# scout_mk1_b.net
KiCad netlist of a schematic drawn in EAGLE
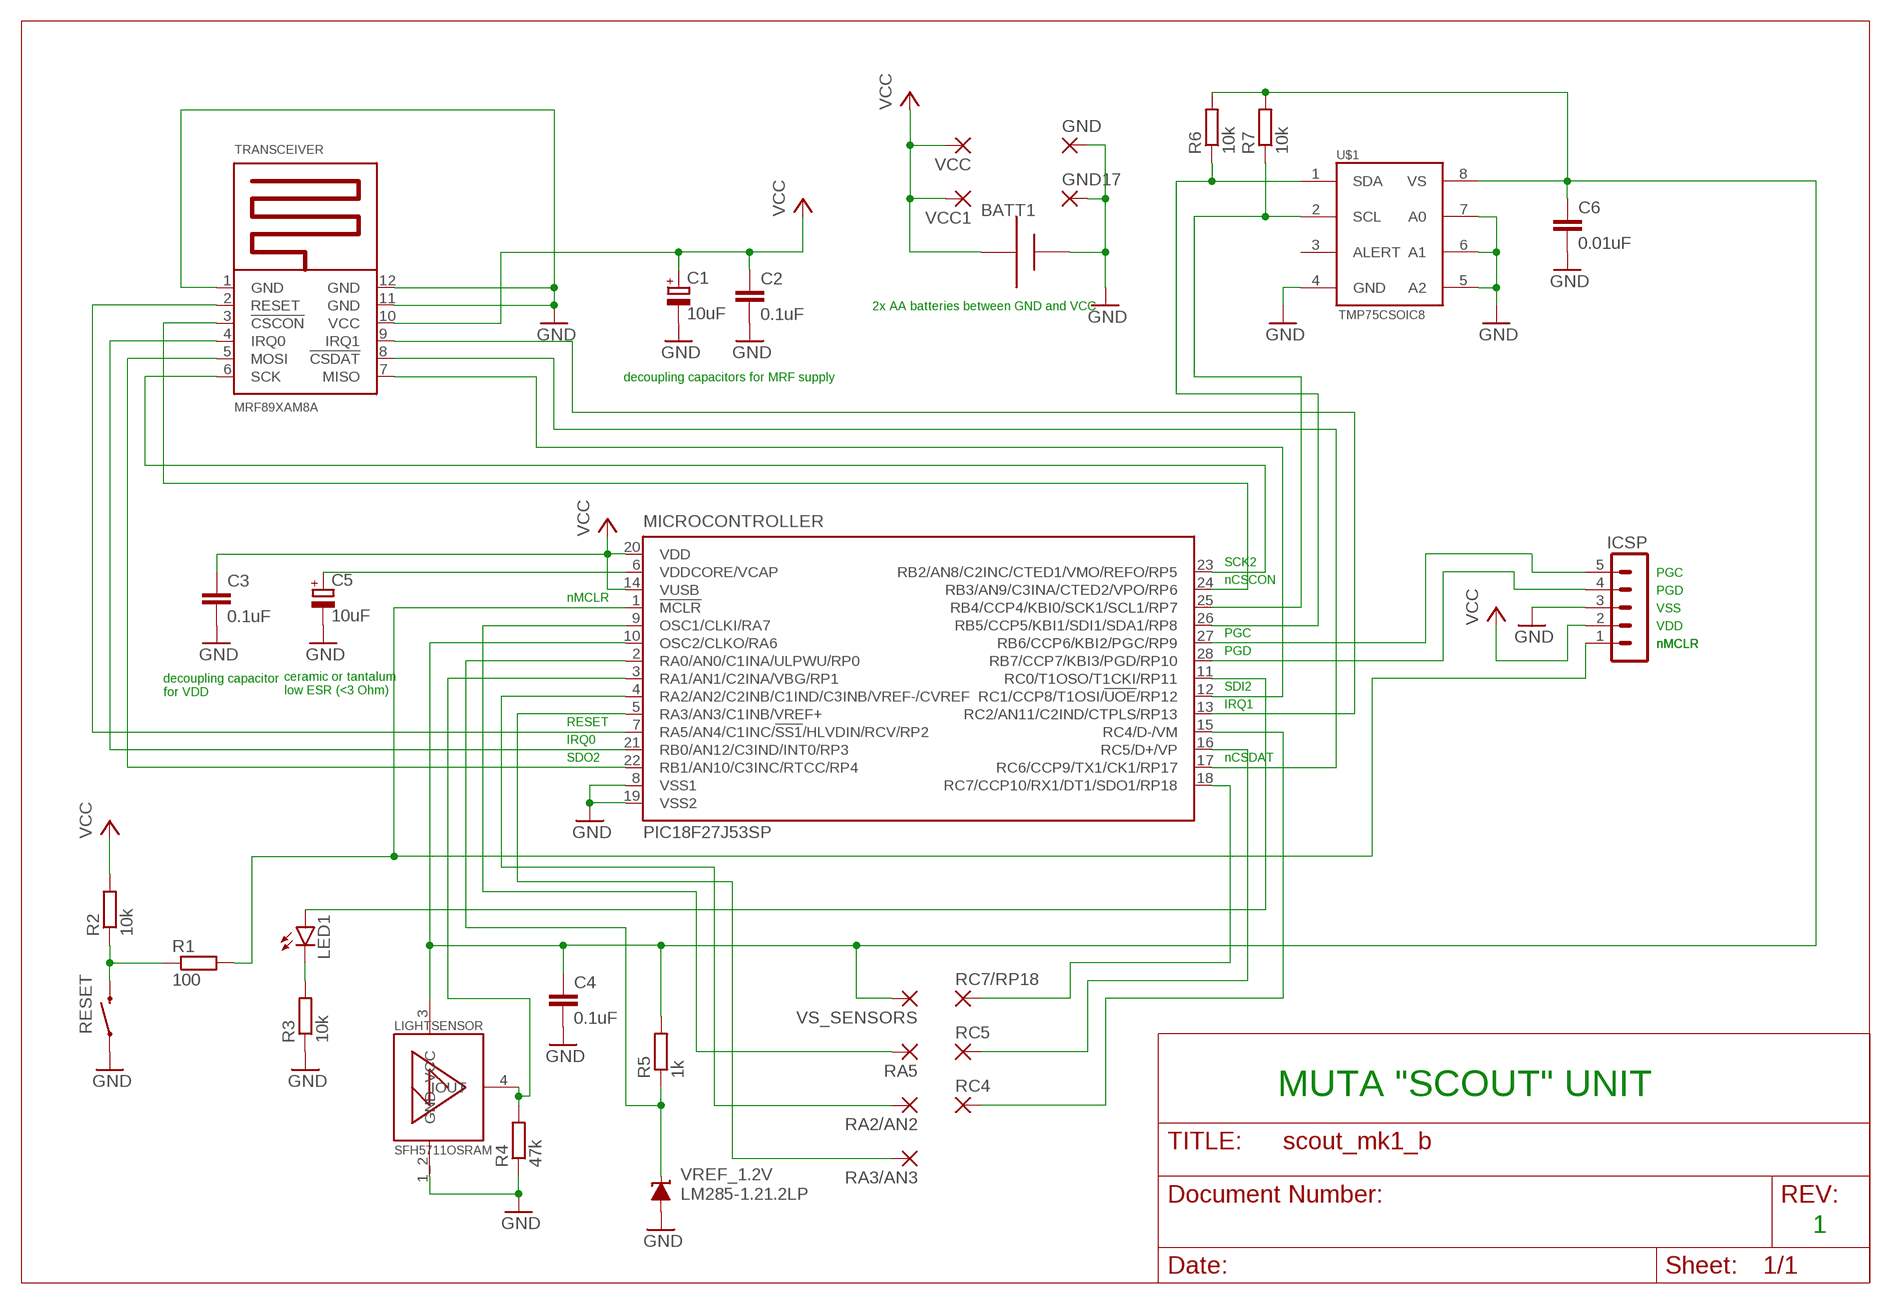
[diagram p0: schematic, sheet 1]

(export (version "E")
  (design (tool "Eeschema 10.0.6"))
  (components
    (comp (ref "BATT1")
      (value "AAA")
      (footprint "eagle-import:2XAAA")
      (libsource (lib "eagle-import") (part "AAA"))
    )
    (comp (ref "C1")
      (value "10uF")
      (footprint "eagle-import:TT5D6")
      (libsource (lib "eagle-import") (part "CPOL-EUTT6D6"))
    )
    (comp (ref "C2")
      (value "0.1uF")
      (footprint "eagle-import:C050-025X075")
      (libsource (lib "eagle-import") (part "C-EU050-025X075"))
    )
    (comp (ref "C3")
      (value "0.1uF")
      (footprint "eagle-import:C050-025X075")
      (libsource (lib "eagle-import") (part "C-EU050-025X075"))
    )
    (comp (ref "C4")
      (value "0.1uF")
      (footprint "eagle-import:C050-025X075")
      (libsource (lib "eagle-import") (part "C-EU050-025X075"))
    )
    (comp (ref "C5")
      (value "10uF")
      (footprint "eagle-import:C_6032-28R")
      (libsource (lib "eagle-import") (part "CPOL-EUC/6032-28R"))
    )
    (comp (ref "C6")
      (value "0.01uF")
      (footprint "eagle-import:C050-025X075")
      (libsource (lib "eagle-import") (part "C-EU050-025X075"))
    )
    (comp (ref "GND")
      (value "3,81/1,1")
      (footprint "eagle-import:3,81_1,1")
      (libsource (lib "eagle-import") (part "3,81/1,1"))
    )
    (comp (ref "GND17")
      (value "3,81/1,1")
      (footprint "eagle-import:3,81_1,1")
      (libsource (lib "eagle-import") (part "3,81/1,1"))
    )
    (comp (ref "ICSP")
      (value "MA05-1")
      (footprint "eagle-import:MA05-1")
      (libsource (lib "eagle-import") (part "MA05-1"))
    )
    (comp (ref "LED1")
      (value "LED1206")
      (footprint "eagle-import:LED-1206")
      (libsource (lib "eagle-import") (part "LED1206"))
    )
    (comp (ref "LIGHTSENSOR")
      (value "SFH5711OSRAM")
      (footprint "eagle-import:SFH5711")
      (libsource (lib "eagle-import") (part "SFH5711OSRAM"))
    )
    (comp (ref "MICROCONTROLLER")
      (value "PIC18F27J53SP")
      (footprint "eagle-import:DIL28-3")
      (fields (field (name "MPN") "PIC18F27J53-I/SP"))
      (libsource (lib "eagle-import") (part "PIC18F2J53SP7"))
    )
    (comp (ref "R1")
      (value "100")
      (footprint "eagle-import:0207_10")
      (libsource (lib "eagle-import") (part "R-EU_0207_10"))
    )
    (comp (ref "R2")
      (value "10k")
      (footprint "eagle-import:0207_10")
      (libsource (lib "eagle-import") (part "R-EU_0207_10"))
    )
    (comp (ref "R3")
      (value "10k")
      (footprint "eagle-import:0207_2V")
      (libsource (lib "eagle-import") (part "R-EU_0207_2V"))
    )
    (comp (ref "R4")
      (value "47k")
      (footprint "eagle-import:0207_10")
      (libsource (lib "eagle-import") (part "R-EU_0207_10"))
    )
    (comp (ref "R5")
      (value "1k")
      (footprint "eagle-import:0207_10")
      (libsource (lib "eagle-import") (part "R-EU_0207_10"))
    )
    (comp (ref "R6")
      (value "10k")
      (footprint "eagle-import:0207_10")
      (libsource (lib "eagle-import") (part "R-EU_0207_10"))
    )
    (comp (ref "R7")
      (value "10k")
      (footprint "eagle-import:0207_10")
      (libsource (lib "eagle-import") (part "R-EU_0207_10"))
    )
    (comp (ref "RA2/AN2")
      (value "3,81/1,1")
      (footprint "eagle-import:3,81_1,1")
      (libsource (lib "eagle-import") (part "3,81/1,1"))
    )
    (comp (ref "RA3/AN3")
      (value "3,81/1,1")
      (footprint "eagle-import:3,81_1,1")
      (libsource (lib "eagle-import") (part "3,81/1,1"))
    )
    (comp (ref "RA5")
      (value "3,81/1,1")
      (footprint "eagle-import:3,81_1,1")
      (libsource (lib "eagle-import") (part "3,81/1,1"))
    )
    (comp (ref "RC4")
      (value "3,81/1,1")
      (footprint "eagle-import:3,81_1,1")
      (libsource (lib "eagle-import") (part "3,81/1,1"))
    )
    (comp (ref "RC5")
      (value "3,81/1,1")
      (footprint "eagle-import:3,81_1,1")
      (libsource (lib "eagle-import") (part "3,81/1,1"))
    )
    (comp (ref "RC7/RP18")
      (value "3,81/1,1")
      (footprint "eagle-import:3,81_1,1")
      (libsource (lib "eagle-import") (part "3,81/1,1"))
    )
    (comp (ref "RESET")
      (value "SWITCH-MOMENTARY-2PTH")
      (footprint "eagle-import:TACTILE-PTH")
      (libsource (lib "eagle-import") (part "SWITCH-MOMENTARY-2PTH"))
    )
    (comp (ref "TRANSCEIVER")
      (value "MRF89XAM8A")
      (footprint "eagle-import:MRF89XAMXA")
      (libsource (lib "eagle-import") (part "MRF89XAM8A"))
    )
    (comp (ref "U$1")
      (value "TMP75CSOIC8")
      (footprint "eagle-import:SOIC8")
      (libsource (lib "eagle-import") (part "TMP75CSOIC8"))
    )
    (comp (ref "VCC")
      (value "3,81/1,1")
      (footprint "eagle-import:3,81_1,1")
      (libsource (lib "eagle-import") (part "3,81/1,1"))
    )
    (comp (ref "VCC1")
      (value "3,81/1,1")
      (footprint "eagle-import:3,81_1,1")
      (libsource (lib "eagle-import") (part "3,81/1,1"))
    )
    (comp (ref "VREF_1.2V")
      (value "LM285-1.21.2LP")
      (footprint "eagle-import:LP_O-PBCY-W3")
      (libsource (lib "eagle-import") (part "LM285-1.21.2LP"))
    )
    (comp (ref "VS_SENSORS")
      (value "3,81/1,1")
      (footprint "eagle-import:3,81_1,1")
      (libsource (lib "eagle-import") (part "3,81/1,1"))
    )
  )
  (nets
    (net (code "1") (name "GND") (class "Default")
      (node (ref "BATT1") (pin "P$1") (pinfunction "+_P$1") (pintype "bidirectional"))
      (node (ref "C1") (pin "-") (pinfunction "-_-") (pintype "passive"))
      (node (ref "C2") (pin "2") (pinfunction "2_2") (pintype "passive"))
      (node (ref "C3") (pin "2") (pinfunction "2_2") (pintype "passive"))
      (node (ref "C4") (pin "2") (pinfunction "2_2") (pintype "passive"))
      (node (ref "C5") (pin "-") (pinfunction "-_-") (pintype "passive"))
      (node (ref "C6") (pin "2") (pinfunction "2_2") (pintype "passive"))
      (node (ref "GND") (pin "1") (pinfunction "P_1") (pintype "passive"))
      (node (ref "GND17") (pin "1") (pinfunction "P_1") (pintype "passive"))
      (node (ref "ICSP") (pin "3") (pinfunction "3_3") (pintype "passive"))
      (node (ref "LIGHTSENSOR") (pin "1_2") (pinfunction "GND_1_2") (pintype "bidirectional"))
      (node (ref "MICROCONTROLLER") (pin "19") (pinfunction "VSS2_19") (pintype "input"))
      (node (ref "MICROCONTROLLER") (pin "8") (pinfunction "VSS1_8") (pintype "input"))
      (node (ref "R3") (pin "1") (pinfunction "1_1") (pintype "passive"))
      (node (ref "R4") (pin "1") (pinfunction "1_1") (pintype "passive"))
      (node (ref "RESET") (pin "1") (pinfunction "1_1") (pintype "passive"))
      (node (ref "TRANSCEIVER") (pin "1") (pinfunction "GND_1") (pintype "power_in"))
      (node (ref "TRANSCEIVER") (pin "11") (pinfunction "GND_11") (pintype "power_in"))
      (node (ref "TRANSCEIVER") (pin "12") (pinfunction "GND_12") (pintype "power_in"))
      (node (ref "U$1") (pin "4") (pinfunction "GND_4") (pintype "bidirectional"))
      (node (ref "U$1") (pin "5") (pinfunction "A2_5") (pintype "bidirectional"))
      (node (ref "U$1") (pin "6") (pinfunction "A1_6") (pintype "bidirectional"))
      (node (ref "U$1") (pin "7") (pinfunction "A0_7") (pintype "bidirectional"))
      (node (ref "VREF_1.2V") (pin "3") (pinfunction "A_3") (pintype "passive"))
    )
    (net (code "2") (name "Net-(LED1-PadC)") (class "Default")
      (node (ref "LED1") (pin "C") (pinfunction "C_C") (pintype "passive"))
      (node (ref "R3") (pin "2") (pinfunction "2_2") (pintype "passive"))
    )
    (net (code "3") (name "Net-(LIGHTSENSOR-IOUT)") (class "Default")
      (node (ref "LIGHTSENSOR") (pin "4") (pinfunction "IOUT_4") (pintype "bidirectional"))
      (node (ref "MICROCONTROLLER") (pin "3") (pinfunction "RA1/AN1/C2INA/VBG/RP1_3") (pintype "bidirectional"))
      (node (ref "R4") (pin "2") (pinfunction "2_2") (pintype "passive"))
    )
    (net (code "4") (name "Net-(LIGHTSENSOR-VCC)") (class "Default")
      (node (ref "C4") (pin "1") (pinfunction "1_1") (pintype "passive"))
      (node (ref "C6") (pin "1") (pinfunction "1_1") (pintype "passive"))
      (node (ref "LIGHTSENSOR") (pin "3") (pinfunction "VCC_3") (pintype "bidirectional"))
      (node (ref "MICROCONTROLLER") (pin "10") (pinfunction "OSC2/CLKO/RA6_10") (pintype "bidirectional"))
      (node (ref "R5") (pin "2") (pinfunction "2_2") (pintype "passive"))
      (node (ref "R6") (pin "2") (pinfunction "2_2") (pintype "passive"))
      (node (ref "R7") (pin "2") (pinfunction "2_2") (pintype "passive"))
      (node (ref "U$1") (pin "8") (pinfunction "VS_8") (pintype "bidirectional"))
      (node (ref "VS_SENSORS") (pin "1") (pinfunction "P_1") (pintype "passive"))
    )
    (net (code "5") (name "Net-(MICROCONTROLLER-OSC1{slash}CLKI{slash}RA7)") (class "Default")
      (node (ref "MICROCONTROLLER") (pin "9") (pinfunction "OSC1/CLKI/RA7_9") (pintype "bidirectional"))
      (node (ref "RA5") (pin "1") (pinfunction "P_1") (pintype "passive"))
    )
    (net (code "6") (name "Net-(MICROCONTROLLER-RA0{slash}AN0{slash}C1INA{slash}ULPWU{slash}RP0)") (class "Default")
      (node (ref "MICROCONTROLLER") (pin "2") (pinfunction "RA0/AN0/C1INA/ULPWU/RP0_2") (pintype "bidirectional"))
      (node (ref "R5") (pin "1") (pinfunction "1_1") (pintype "passive"))
      (node (ref "VREF_1.2V") (pin "2") (pinfunction "C_2") (pintype "passive"))
    )
    (net (code "7") (name "Net-(MICROCONTROLLER-RA2{slash}AN2{slash}C2INB{slash}C1IND{slash}C3INB{slash}VREF-{slash}CVREF)") (class "Default")
      (node (ref "MICROCONTROLLER") (pin "4") (pinfunction "RA2/AN2/C2INB/C1IND/C3INB/VREF-/CVREF_4") (pintype "bidirectional"))
      (node (ref "RA2/AN2") (pin "1") (pinfunction "P_1") (pintype "passive"))
    )
    (net (code "8") (name "Net-(MICROCONTROLLER-RA3{slash}AN3{slash}C1INB{slash}VREF+)") (class "Default")
      (node (ref "MICROCONTROLLER") (pin "5") (pinfunction "RA3/AN3/C1INB/VREF+_5") (pintype "bidirectional"))
      (node (ref "RA3/AN3") (pin "1") (pinfunction "P_1") (pintype "passive"))
    )
    (net (code "9") (name "Net-(MICROCONTROLLER-RA5{slash}AN4{slash}C1INC{slash}~{SS1}{slash}HLVDIN{slash}RCV{slash}RP2)") (class "Default")
      (node (ref "MICROCONTROLLER") (pin "7") (pinfunction "RA5/AN4/C1INC/~{SS1}/HLVDIN/RCV/RP2_7") (pintype "bidirectional"))
      (node (ref "TRANSCEIVER") (pin "2") (pinfunction "RESET_2") (pintype "input"))
    )
    (net (code "10") (name "Net-(MICROCONTROLLER-RB0{slash}AN12{slash}C3IND{slash}INT0{slash}RP3)") (class "Default")
      (node (ref "MICROCONTROLLER") (pin "21") (pinfunction "RB0/AN12/C3IND/INT0/RP3_21") (pintype "bidirectional"))
      (node (ref "TRANSCEIVER") (pin "4") (pinfunction "IRQ0_4") (pintype "output"))
    )
    (net (code "11") (name "Net-(MICROCONTROLLER-RB1{slash}AN10{slash}C3INC{slash}RTCC{slash}RP4)") (class "Default")
      (node (ref "MICROCONTROLLER") (pin "22") (pinfunction "RB1/AN10/C3INC/RTCC/RP4_22") (pintype "bidirectional"))
      (node (ref "TRANSCEIVER") (pin "5") (pinfunction "MOSI_5") (pintype "input"))
    )
    (net (code "12") (name "Net-(MICROCONTROLLER-RB2{slash}AN8{slash}C2INC{slash}CTED1{slash}VMO{slash}REFO{slash}RP5)") (class "Default")
      (node (ref "MICROCONTROLLER") (pin "23") (pinfunction "RB2/AN8/C2INC/CTED1/VMO/REFO/RP5_23") (pintype "bidirectional"))
      (node (ref "TRANSCEIVER") (pin "6") (pinfunction "SCK_6") (pintype "input"))
    )
    (net (code "13") (name "Net-(MICROCONTROLLER-RB3{slash}AN9{slash}C3INA{slash}CTED2{slash}VPO{slash}RP6)") (class "Default")
      (node (ref "MICROCONTROLLER") (pin "24") (pinfunction "RB3/AN9/C3INA/CTED2/VPO/RP6_24") (pintype "bidirectional"))
      (node (ref "TRANSCEIVER") (pin "3") (pinfunction "~{CSCON}_3") (pintype "input"))
    )
    (net (code "14") (name "Net-(MICROCONTROLLER-RB4{slash}CCP4{slash}KBI0{slash}SCK1{slash}SCL1{slash}RP7)") (class "Default")
      (node (ref "MICROCONTROLLER") (pin "25") (pinfunction "RB4/CCP4/KBI0/SCK1/SCL1/RP7_25") (pintype "bidirectional"))
      (node (ref "R7") (pin "1") (pinfunction "1_1") (pintype "passive"))
      (node (ref "U$1") (pin "2") (pinfunction "SCL_2") (pintype "bidirectional"))
    )
    (net (code "15") (name "Net-(MICROCONTROLLER-RB5{slash}CCP5{slash}KBI1{slash}SDI1{slash}SDA1{slash}RP8)") (class "Default")
      (node (ref "MICROCONTROLLER") (pin "26") (pinfunction "RB5/CCP5/KBI1/SDI1/SDA1/RP8_26") (pintype "bidirectional"))
      (node (ref "R6") (pin "1") (pinfunction "1_1") (pintype "passive"))
      (node (ref "U$1") (pin "1") (pinfunction "SDA_1") (pintype "bidirectional"))
    )
    (net (code "16") (name "Net-(MICROCONTROLLER-RB6{slash}CCP6{slash}KBI2{slash}PGC{slash}RP9)") (class "Default")
      (node (ref "ICSP") (pin "5") (pinfunction "5_5") (pintype "passive"))
      (node (ref "MICROCONTROLLER") (pin "27") (pinfunction "RB6/CCP6/KBI2/PGC/RP9_27") (pintype "bidirectional"))
    )
    (net (code "17") (name "Net-(MICROCONTROLLER-RB7{slash}CCP7{slash}KBI3{slash}PGD{slash}RP10)") (class "Default")
      (node (ref "ICSP") (pin "4") (pinfunction "4_4") (pintype "passive"))
      (node (ref "MICROCONTROLLER") (pin "28") (pinfunction "RB7/CCP7/KBI3/PGD/RP10_28") (pintype "bidirectional"))
    )
    (net (code "18") (name "Net-(MICROCONTROLLER-RC0{slash}T1OSO{slash}T1CKI{slash}RP11)") (class "Default")
      (node (ref "LED1") (pin "A") (pinfunction "A_A") (pintype "passive"))
      (node (ref "MICROCONTROLLER") (pin "11") (pinfunction "RC0/T1OSO/T1CKI/RP11_11") (pintype "bidirectional"))
    )
    (net (code "19") (name "Net-(MICROCONTROLLER-RC1{slash}CCP8{slash}T1OSI{slash}~{UOE}{slash}RP12)") (class "Default")
      (node (ref "MICROCONTROLLER") (pin "12") (pinfunction "RC1/CCP8/T1OSI/~{UOE}/RP12_12") (pintype "bidirectional"))
      (node (ref "TRANSCEIVER") (pin "7") (pinfunction "MISO_7") (pintype "output"))
    )
    (net (code "20") (name "Net-(MICROCONTROLLER-RC2{slash}AN11{slash}C2IND{slash}CTPLS{slash}RP13)") (class "Default")
      (node (ref "MICROCONTROLLER") (pin "13") (pinfunction "RC2/AN11/C2IND/CTPLS/RP13_13") (pintype "bidirectional"))
      (node (ref "TRANSCEIVER") (pin "9") (pinfunction "IRQ1_9") (pintype "output"))
    )
    (net (code "21") (name "Net-(MICROCONTROLLER-RC4{slash}D-{slash}VM)") (class "Default")
      (node (ref "MICROCONTROLLER") (pin "15") (pinfunction "RC4/D-/VM_15") (pintype "bidirectional"))
      (node (ref "RC4") (pin "1") (pinfunction "P_1") (pintype "passive"))
    )
    (net (code "22") (name "Net-(MICROCONTROLLER-RC5{slash}D+{slash}VP)") (class "Default")
      (node (ref "MICROCONTROLLER") (pin "16") (pinfunction "RC5/D+/VP_16") (pintype "bidirectional"))
      (node (ref "RC5") (pin "1") (pinfunction "P_1") (pintype "passive"))
    )
    (net (code "23") (name "Net-(MICROCONTROLLER-RC6{slash}CCP9{slash}TX1{slash}CK1{slash}RP17)") (class "Default")
      (node (ref "MICROCONTROLLER") (pin "17") (pinfunction "RC6/CCP9/TX1/CK1/RP17_17") (pintype "bidirectional"))
      (node (ref "TRANSCEIVER") (pin "8") (pinfunction "~{CSDAT}_8") (pintype "input"))
    )
    (net (code "24") (name "Net-(MICROCONTROLLER-RC7{slash}CCP10{slash}RX1{slash}DT1{slash}SDO1{slash}RP18)") (class "Default")
      (node (ref "MICROCONTROLLER") (pin "18") (pinfunction "RC7/CCP10/RX1/DT1/SDO1/RP18_18") (pintype "bidirectional"))
      (node (ref "RC7/RP18") (pin "1") (pinfunction "P_1") (pintype "passive"))
    )
    (net (code "25") (name "Net-(MICROCONTROLLER-VDDCORE{slash}VCAP)") (class "Default")
      (node (ref "C5") (pin "+") (pinfunction "+_+") (pintype "passive"))
      (node (ref "MICROCONTROLLER") (pin "6") (pinfunction "VDDCORE/VCAP_6") (pintype "input"))
    )
    (net (code "26") (name "Net-(MICROCONTROLLER-~{MCLR})") (class "Default")
      (node (ref "ICSP") (pin "1") (pinfunction "1_1") (pintype "passive"))
      (node (ref "MICROCONTROLLER") (pin "1") (pinfunction "~{MCLR}_1") (pintype "input"))
      (node (ref "R1") (pin "2") (pinfunction "2_2") (pintype "passive"))
    )
    (net (code "27") (name "Net-(RESET-2)") (class "Default")
      (node (ref "R1") (pin "1") (pinfunction "1_1") (pintype "passive"))
      (node (ref "R2") (pin "1") (pinfunction "1_1") (pintype "passive"))
      (node (ref "RESET") (pin "3") (pinfunction "2_3") (pintype "passive"))
    )
    (net (code "28") (name "VCC") (class "Default")
      (node (ref "BATT1") (pin "P$2") (pinfunction "-_P$2") (pintype "bidirectional"))
      (node (ref "C1") (pin "+") (pinfunction "+_+") (pintype "passive"))
      (node (ref "C2") (pin "1") (pinfunction "1_1") (pintype "passive"))
      (node (ref "C3") (pin "1") (pinfunction "1_1") (pintype "passive"))
      (node (ref "ICSP") (pin "2") (pinfunction "2_2") (pintype "passive"))
      (node (ref "MICROCONTROLLER") (pin "14") (pinfunction "VUSB_14") (pintype "input"))
      (node (ref "MICROCONTROLLER") (pin "20") (pinfunction "VDD_20") (pintype "input"))
      (node (ref "R2") (pin "2") (pinfunction "2_2") (pintype "passive"))
      (node (ref "TRANSCEIVER") (pin "10") (pinfunction "VCC_10") (pintype "power_in"))
      (node (ref "VCC") (pin "1") (pinfunction "P_1") (pintype "passive"))
      (node (ref "VCC1") (pin "1") (pinfunction "P_1") (pintype "passive"))
    )
    (net (code "29") (name "unconnected-(U$1-ALERT-Pad3)") (class "Default")
      (node (ref "U$1") (pin "3") (pinfunction "ALERT_3") (pintype "bidirectional"))
    )
  )
)
